# ROBOT.net
KiCad netlist of a schematic drawn in Altium Designer
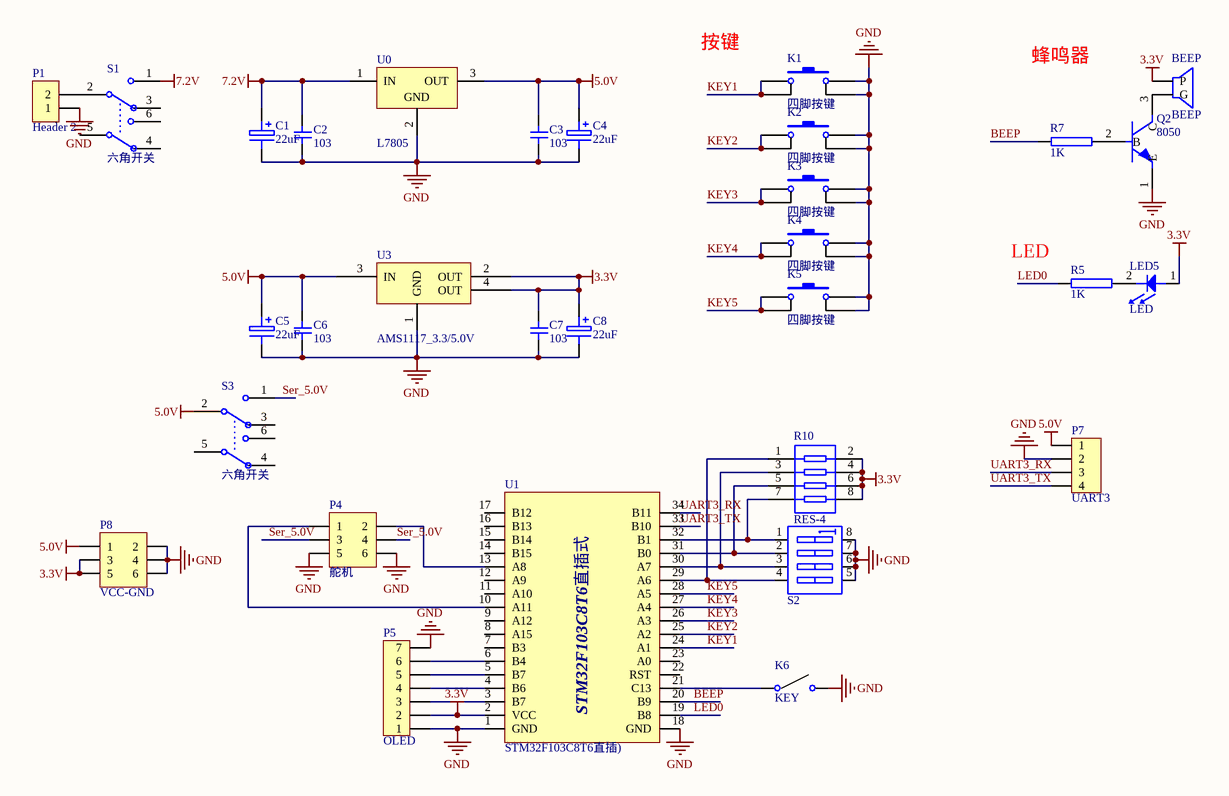
[diagram p0: ROBOT.SchDoc]

(export (version "E")
  (design (tool "Eeschema 10.0.6"))
  (components
    (comp (ref "BEEP") (value "BEEP") (footprint "BUZZER") (libsource (lib "EXPLORER") (part "BEEP")))
    (comp (ref "C1") (value "22uF") (footprint "Cap1(47uF)") (libsource (lib "窝牛器件封装") (part "Cap1(100uF)")))
    (comp (ref "C2") (value "103") (footprint "0805C") (libsource (lib "窝牛器件封装") (part "C1")))
    (comp (ref "C3") (value "103") (footprint "0805C") (libsource (lib "窝牛器件封装") (part "C1")))
    (comp (ref "C4") (value "22uF") (footprint "Cap1(47uF)") (libsource (lib "窝牛器件封装") (part "Cap1(100uF)")))
    (comp (ref "C5") (value "22uF") (footprint "Cap1(47uF)") (libsource (lib "窝牛器件封装") (part "Cap1(100uF)")))
    (comp (ref "C6") (value "103") (footprint "0805C") (libsource (lib "窝牛器件封装") (part "C1")))
    (comp (ref "C7") (value "103") (footprint "0805C") (libsource (lib "窝牛器件封装") (part "C1")))
    (comp (ref "C8") (value "22uF") (footprint "Cap1(47uF)") (libsource (lib "窝牛器件封装") (part "Cap1(100uF)")))
    (comp (ref "K1") (value "四脚按键") (footprint "SW_PB4_DIP") (libsource (lib "窝牛器件封装") (part "Key(四脚)")))
    (comp (ref "K2") (value "四脚按键") (footprint "SW_PB4_DIP") (libsource (lib "窝牛器件封装") (part "Key(四脚)")))
    (comp (ref "K3") (value "四脚按键") (footprint "SW_PB4_DIP") (libsource (lib "窝牛器件封装") (part "Key(四脚)")))
    (comp (ref "K4") (value "四脚按键") (footprint "SW_PB4_DIP") (libsource (lib "窝牛器件封装") (part "Key(四脚)")))
    (comp (ref "K5") (value "四脚按键") (footprint "SW_PB4_DIP") (libsource (lib "窝牛器件封装") (part "Key(四脚)")))
    (comp (ref "K6") (value "KEY") (footprint "干簧管") (libsource (lib "JMU智能车专用3.0.4") (part "干簧管")))
    (comp (ref "LED5") (value "LED") (footprint "0805LED") (libsource (lib "窝牛器件封装") (part "LED")))
    (comp (ref "P1") (value "Header 2") (footprint "Header 2") (libsource (lib "窝牛器件封装") (part "Header 2")))
    (comp (ref "P4") (value "舵机") (footprint "Header 3X2") (libsource (lib "窝牛器件封装") (part "Header 3X2")))
    (comp (ref "P5") (value "OLED") (footprint "Header 7") (libsource (lib "窝牛器件封装") (part "Header 7")))
    (comp (ref "P7") (value "UART3") (footprint "Header 4") (libsource (lib "窝牛器件封装") (part "Header 4")))
    (comp (ref "P8")
      (value "VCC-GND")
      (footprint "Header 3X2")
      (libsource (lib "窝牛器件封装") (part "Header 3X2"))
    )
    (comp (ref "Q2") (value "8050") (footprint "NPN") (libsource (lib "窝牛器件封装") (part "Q2")))
    (comp (ref "R5") (value "1K") (footprint "0805R") (libsource (lib "窝牛器件封装") (part "R1")))
    (comp (ref "R7") (value "1K") (footprint "0805R") (libsource (lib "窝牛器件封装") (part "R1")))
    (comp (ref "R10") (value "RES-4") (footprint "排阻(4位贴片)") (libsource (lib "窝牛器件封装") (part "RES-4")))
    (comp (ref "S1") (value "六角开关") (footprint "六角开关") (libsource (lib "窝牛器件封装") (part "六角开关")))
    (comp (ref "S2")
      (value "SWICH")
      (footprint "拨码开关*4")
      (description "拨码开关（4位）")
      (libsource (lib "JMU智能车专用3.0.4") (part "拨码开关(4位)"))
    )
    (comp (ref "S3") (value "六角开关") (footprint "六角开关") (libsource (lib "窝牛器件封装") (part "六角开关")))
    (comp (ref "U0") (value "L7805") (footprint "T03B") (libsource (lib "窝牛器件封装") (part "L7805")))
    (comp (ref "U1")
      (value "STM32F103C8T6直插)")
      (footprint "ST32F103C8T6直插")
      (libsource (lib "窝牛器件封装") (part "STM32F103C8T6直插)"))
    )
    (comp (ref "U3")
      (value "AMS1117_3.3/5.0V")
      (footprint "SOT-223")
      (libsource (lib "窝牛器件封装") (part "AMS1117-3.3V/5.0V"))
    )
  )
  (nets
    (net (code "1") (name "/BEEP") (class "Default")
      (node (ref "R7") (pin "2") (pinfunction "2_2") (pintype "passive"))
      (node (ref "U1") (pin "20") (pinfunction "B9_20") (pintype "passive"))
    )
    (net (code "2") (name "/KEY1") (class "Default")
      (node (ref "K1") (pin "1") (pinfunction "1_1") (pintype "passive"))
      (node (ref "K1") (pin "4") (pinfunction "4_4") (pintype "passive"))
      (node (ref "U1") (pin "24") (pinfunction "A1_24") (pintype "passive"))
    )
    (net (code "3") (name "/KEY2") (class "Default")
      (node (ref "K2") (pin "1") (pinfunction "1_1") (pintype "passive"))
      (node (ref "K2") (pin "4") (pinfunction "4_4") (pintype "passive"))
      (node (ref "U1") (pin "25") (pinfunction "A2_25") (pintype "passive"))
    )
    (net (code "4") (name "/KEY3") (class "Default")
      (node (ref "K3") (pin "1") (pinfunction "1_1") (pintype "passive"))
      (node (ref "K3") (pin "4") (pinfunction "4_4") (pintype "passive"))
      (node (ref "U1") (pin "26") (pinfunction "A3_26") (pintype "passive"))
    )
    (net (code "5") (name "/KEY4") (class "Default")
      (node (ref "K4") (pin "1") (pinfunction "1_1") (pintype "passive"))
      (node (ref "K4") (pin "4") (pinfunction "4_4") (pintype "passive"))
      (node (ref "U1") (pin "27") (pinfunction "A4_27") (pintype "passive"))
    )
    (net (code "6") (name "/KEY5") (class "Default")
      (node (ref "K5") (pin "1") (pinfunction "1_1") (pintype "passive"))
      (node (ref "K5") (pin "4") (pinfunction "4_4") (pintype "passive"))
      (node (ref "U1") (pin "28") (pinfunction "A5_28") (pintype "passive"))
    )
    (net (code "7") (name "/LED0") (class "Default")
      (node (ref "R5") (pin "2") (pinfunction "2_2") (pintype "passive"))
      (node (ref "U1") (pin "19") (pinfunction "B8_19") (pintype "passive"))
    )
    (net (code "8") (name "/Ser_5.0V") (class "Default")
      (node (ref "P4") (pin "3") (pinfunction "3_3") (pintype "passive"))
      (node (ref "P4") (pin "4") (pinfunction "4_4") (pintype "passive"))
      (node (ref "S3") (pin "1") (pinfunction "1_1") (pintype "passive"))
    )
    (net (code "9") (name "/UART3_RX") (class "Default")
      (node (ref "P7") (pin "3") (pinfunction "3_3") (pintype "passive"))
      (node (ref "U1") (pin "34") (pinfunction "B11_34") (pintype "passive"))
    )
    (net (code "10") (name "/UART3_TX") (class "Default")
      (node (ref "P7") (pin "4") (pinfunction "4_4") (pintype "passive"))
      (node (ref "U1") (pin "33") (pinfunction "B10_33") (pintype "passive"))
    )
    (net (code "11") (name "3.3V") (class "Default")
      (node (ref "BEEP") (pin "1") (pinfunction "P_1") (pintype "passive"))
      (node (ref "C7") (pin "2") (pinfunction "2_2") (pintype "passive"))
      (node (ref "C8") (pin "1") (pinfunction "1_1") (pintype "passive"))
      (node (ref "LED5") (pin "1") (pinfunction "1_1") (pintype "passive"))
      (node (ref "P5") (pin "2") (pinfunction "2_2") (pintype "passive"))
      (node (ref "P8") (pin "3") (pinfunction "3_3") (pintype "passive"))
      (node (ref "P8") (pin "5") (pinfunction "5_5") (pintype "passive"))
      (node (ref "R10") (pin "2") (pinfunction "2_2") (pintype "passive"))
      (node (ref "R10") (pin "4") (pinfunction "4_4") (pintype "passive"))
      (node (ref "R10") (pin "6") (pinfunction "6_6") (pintype "passive"))
      (node (ref "R10") (pin "8") (pinfunction "8_8") (pintype "passive"))
      (node (ref "U1") (pin "2") (pinfunction "VCC_2") (pintype "passive"))
      (node (ref "U3") (pin "2") (pinfunction "OUT_2") (pintype "passive"))
      (node (ref "U3") (pin "4") (pinfunction "OUT_4") (pintype "passive"))
    )
    (net (code "12") (name "5.0V") (class "Default")
      (node (ref "C3") (pin "2") (pinfunction "2_2") (pintype "passive"))
      (node (ref "C4") (pin "1") (pinfunction "1_1") (pintype "passive"))
      (node (ref "C5") (pin "1") (pinfunction "1_1") (pintype "passive"))
      (node (ref "C6") (pin "2") (pinfunction "2_2") (pintype "passive"))
      (node (ref "P7") (pin "1") (pinfunction "1_1") (pintype "passive"))
      (node (ref "P8") (pin "1") (pinfunction "1_1") (pintype "passive"))
      (node (ref "S3") (pin "2") (pinfunction "2_2") (pintype "passive"))
      (node (ref "U0") (pin "3") (pinfunction "OUT_3") (pintype "power_in"))
      (node (ref "U3") (pin "3") (pinfunction "IN_3") (pintype "passive"))
    )
    (net (code "13") (name "7.2V") (class "Default")
      (node (ref "C1") (pin "1") (pinfunction "1_1") (pintype "passive"))
      (node (ref "C2") (pin "2") (pinfunction "2_2") (pintype "passive"))
      (node (ref "S1") (pin "1") (pinfunction "1_1") (pintype "passive"))
      (node (ref "U0") (pin "1") (pinfunction "IN_1") (pintype "power_in"))
    )
    (net (code "14") (name "GND") (class "Default")
      (node (ref "C1") (pin "2") (pinfunction "2_2") (pintype "passive"))
      (node (ref "C2") (pin "1") (pinfunction "1_1") (pintype "passive"))
      (node (ref "C3") (pin "1") (pinfunction "1_1") (pintype "passive"))
      (node (ref "C4") (pin "2") (pinfunction "2_2") (pintype "passive"))
      (node (ref "C5") (pin "2") (pinfunction "2_2") (pintype "passive"))
      (node (ref "C6") (pin "1") (pinfunction "1_1") (pintype "passive"))
      (node (ref "C7") (pin "1") (pinfunction "1_1") (pintype "passive"))
      (node (ref "C8") (pin "2") (pinfunction "2_2") (pintype "passive"))
      (node (ref "K1") (pin "2") (pinfunction "2_2") (pintype "passive"))
      (node (ref "K1") (pin "3") (pinfunction "3_3") (pintype "passive"))
      (node (ref "K2") (pin "2") (pinfunction "2_2") (pintype "passive"))
      (node (ref "K2") (pin "3") (pinfunction "3_3") (pintype "passive"))
      (node (ref "K3") (pin "2") (pinfunction "2_2") (pintype "passive"))
      (node (ref "K3") (pin "3") (pinfunction "3_3") (pintype "passive"))
      (node (ref "K4") (pin "2") (pinfunction "2_2") (pintype "passive"))
      (node (ref "K4") (pin "3") (pinfunction "3_3") (pintype "passive"))
      (node (ref "K5") (pin "2") (pinfunction "2_2") (pintype "passive"))
      (node (ref "K5") (pin "3") (pinfunction "3_3") (pintype "passive"))
      (node (ref "K6") (pin "2") (pinfunction "2_2") (pintype "passive"))
      (node (ref "P1") (pin "1") (pinfunction "1_1") (pintype "passive"))
      (node (ref "P4") (pin "5") (pinfunction "5_5") (pintype "passive"))
      (node (ref "P4") (pin "6") (pinfunction "6_6") (pintype "passive"))
      (node (ref "P5") (pin "1") (pinfunction "1_1") (pintype "passive"))
      (node (ref "P5") (pin "7") (pinfunction "7_7") (pintype "passive"))
      (node (ref "P7") (pin "2") (pinfunction "2_2") (pintype "passive"))
      (node (ref "P8") (pin "2") (pinfunction "2_2") (pintype "passive"))
      (node (ref "P8") (pin "4") (pinfunction "4_4") (pintype "passive"))
      (node (ref "P8") (pin "6") (pinfunction "6_6") (pintype "passive"))
      (node (ref "Q2") (pin "1") (pinfunction "E_1") (pintype "passive"))
      (node (ref "S2") (pin "5") (pinfunction "B4_5") (pintype "passive"))
      (node (ref "S2") (pin "6") (pinfunction "B3_6") (pintype "passive"))
      (node (ref "S2") (pin "7") (pinfunction "B2_7") (pintype "passive"))
      (node (ref "S2") (pin "8") (pinfunction "B1_8") (pintype "passive"))
      (node (ref "U0") (pin "2") (pinfunction "GND_2") (pintype "power_in"))
      (node (ref "U1") (pin "1") (pinfunction "GND_1") (pintype "passive"))
      (node (ref "U1") (pin "18") (pinfunction "GND_18") (pintype "passive"))
      (node (ref "U3") (pin "1") (pinfunction "GND_1") (pintype "passive"))
    )
    (net (code "15") (name "Net-(BEEP-G)") (class "Default")
      (node (ref "BEEP") (pin "2") (pinfunction "G_2") (pintype "passive"))
      (node (ref "Q2") (pin "3") (pinfunction "C_3") (pintype "passive"))
    )
    (net (code "16") (name "Net-(LED5-Pad2)") (class "Default")
      (node (ref "LED5") (pin "2") (pinfunction "2_2") (pintype "passive"))
      (node (ref "R5") (pin "1") (pinfunction "1_1") (pintype "passive"))
    )
    (net (code "17") (name "Net-(P1-Pad2)") (class "Default")
      (node (ref "P1") (pin "2") (pinfunction "2_2") (pintype "passive"))
      (node (ref "S1") (pin "2") (pinfunction "2_2") (pintype "passive"))
    )
    (net (code "18") (name "Net-(P5-Pad3)") (class "Default")
      (node (ref "P5") (pin "3") (pinfunction "3_3") (pintype "passive"))
      (node (ref "U1") (pin "3") (pinfunction "B7_3") (pintype "passive"))
    )
    (net (code "19") (name "Net-(P5-Pad5)") (class "Default")
      (node (ref "P5") (pin "5") (pinfunction "5_5") (pintype "passive"))
      (node (ref "U1") (pin "5") (pinfunction "B7_5") (pintype "passive"))
    )
    (net (code "20") (name "Net-(Q2-B)") (class "Default")
      (node (ref "Q2") (pin "2") (pinfunction "B_2") (pintype "passive"))
      (node (ref "R7") (pin "1") (pinfunction "1_1") (pintype "passive"))
    )
    (net (code "21") (name "Net-(S2-A1)") (class "Default")
      (node (ref "R10") (pin "7") (pinfunction "7_7") (pintype "passive"))
      (node (ref "S2") (pin "1") (pinfunction "A1_1") (pintype "passive"))
      (node (ref "U1") (pin "32") (pinfunction "B1_32") (pintype "passive"))
    )
    (net (code "22") (name "Net-(S2-A2)") (class "Default")
      (node (ref "R10") (pin "5") (pinfunction "5_5") (pintype "passive"))
      (node (ref "S2") (pin "2") (pinfunction "A2_2") (pintype "passive"))
      (node (ref "U1") (pin "31") (pinfunction "B0_31") (pintype "passive"))
    )
    (net (code "23") (name "Net-(S2-A3)") (class "Default")
      (node (ref "R10") (pin "3") (pinfunction "3_3") (pintype "passive"))
      (node (ref "S2") (pin "3") (pinfunction "A3_3") (pintype "passive"))
      (node (ref "U1") (pin "30") (pinfunction "A7_30") (pintype "passive"))
    )
    (net (code "24") (name "Net-(S2-A4)") (class "Default")
      (node (ref "R10") (pin "1") (pinfunction "1_1") (pintype "passive"))
      (node (ref "S2") (pin "4") (pinfunction "A4_4") (pintype "passive"))
      (node (ref "U1") (pin "29") (pinfunction "A6_29") (pintype "passive"))
    )
    (net (code "25") (name "Net-(U1-A8)") (class "Default")
      (node (ref "P4") (pin "2") (pinfunction "2_2") (pintype "passive"))
      (node (ref "U1") (pin "13") (pinfunction "A8_13") (pintype "passive"))
    )
    (net (code "26") (name "Net-(U1-A11)") (class "Default")
      (node (ref "P4") (pin "1") (pinfunction "1_1") (pintype "passive"))
      (node (ref "U1") (pin "10") (pinfunction "A11_10") (pintype "passive"))
    )
    (net (code "27") (name "Net-(U1-B4)") (class "Default")
      (node (ref "P5") (pin "6") (pinfunction "6_6") (pintype "passive"))
      (node (ref "U1") (pin "6") (pinfunction "B4_6") (pintype "passive"))
    )
    (net (code "28") (name "Net-(U1-B6)") (class "Default")
      (node (ref "P5") (pin "4") (pinfunction "4_4") (pintype "passive"))
      (node (ref "U1") (pin "4") (pinfunction "B6_4") (pintype "passive"))
    )
    (net (code "29") (name "Net-(U1-C13)") (class "Default")
      (node (ref "K6") (pin "1") (pinfunction "1_1") (pintype "passive"))
      (node (ref "U1") (pin "21") (pinfunction "C13_21") (pintype "passive"))
    )
    (net (code "30") (name "unconnected-(S1-Pad3)") (class "Default")
      (node (ref "S1") (pin "3") (pinfunction "3_3") (pintype "passive"))
    )
    (net (code "31") (name "unconnected-(S1-Pad4)") (class "Default")
      (node (ref "S1") (pin "4") (pinfunction "4_4") (pintype "passive"))
    )
    (net (code "32") (name "unconnected-(S1-Pad5)") (class "Default")
      (node (ref "S1") (pin "5") (pinfunction "5_5") (pintype "passive"))
    )
    (net (code "33") (name "unconnected-(S1-Pad6)") (class "Default")
      (node (ref "S1") (pin "6") (pinfunction "6_6") (pintype "passive"))
    )
    (net (code "34") (name "unconnected-(S3-Pad3)") (class "Default")
      (node (ref "S3") (pin "3") (pinfunction "3_3") (pintype "passive"))
    )
    (net (code "35") (name "unconnected-(S3-Pad4)") (class "Default")
      (node (ref "S3") (pin "4") (pinfunction "4_4") (pintype "passive"))
    )
    (net (code "36") (name "unconnected-(S3-Pad5)") (class "Default")
      (node (ref "S3") (pin "5") (pinfunction "5_5") (pintype "passive"))
    )
    (net (code "37") (name "unconnected-(S3-Pad6)") (class "Default")
      (node (ref "S3") (pin "6") (pinfunction "6_6") (pintype "passive"))
    )
    (net (code "38") (name "unconnected-(U1-A0-Pad23)") (class "Default")
      (node (ref "U1") (pin "23") (pinfunction "A0_23") (pintype "passive"))
    )
    (net (code "39") (name "unconnected-(U1-A9-Pad12)") (class "Default")
      (node (ref "U1") (pin "12") (pinfunction "A9_12") (pintype "passive"))
    )
    (net (code "40") (name "unconnected-(U1-A10-Pad11)") (class "Default")
      (node (ref "U1") (pin "11") (pinfunction "A10_11") (pintype "passive"))
    )
    (net (code "41") (name "unconnected-(U1-A12-Pad9)") (class "Default")
      (node (ref "U1") (pin "9") (pinfunction "A12_9") (pintype "passive"))
    )
    (net (code "42") (name "unconnected-(U1-A15-Pad8)") (class "Default")
      (node (ref "U1") (pin "8") (pinfunction "A15_8") (pintype "passive"))
    )
    (net (code "43") (name "unconnected-(U1-B3-Pad7)") (class "Default")
      (node (ref "U1") (pin "7") (pinfunction "B3_7") (pintype "passive"))
    )
    (net (code "44") (name "unconnected-(U1-B12-Pad17)") (class "Default")
      (node (ref "U1") (pin "17") (pinfunction "B12_17") (pintype "passive"))
    )
    (net (code "45") (name "unconnected-(U1-B13-Pad16)") (class "Default")
      (node (ref "U1") (pin "16") (pinfunction "B13_16") (pintype "passive"))
    )
    (net (code "46") (name "unconnected-(U1-B14-Pad15)") (class "Default")
      (node (ref "U1") (pin "15") (pinfunction "B14_15") (pintype "passive"))
    )
    (net (code "47") (name "unconnected-(U1-B15-Pad14)") (class "Default")
      (node (ref "U1") (pin "14") (pinfunction "B15_14") (pintype "passive"))
    )
    (net (code "48") (name "unconnected-(U1-RST-Pad22)") (class "Default")
      (node (ref "U1") (pin "22") (pinfunction "RST_22") (pintype "passive"))
    )
  )
)
